# ORD_CH341A.net
KiCad netlist of a schematic drawn in Altium Designer
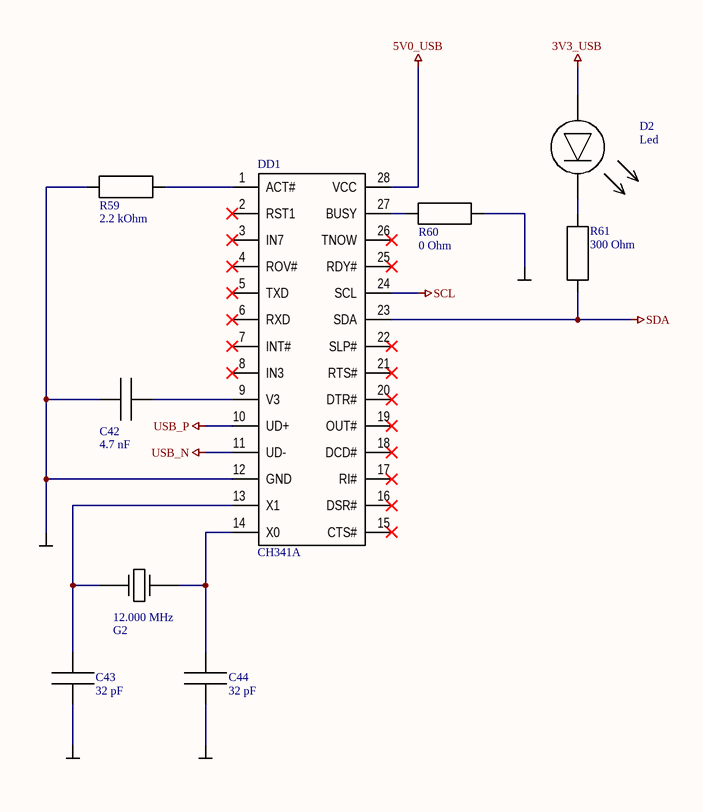
[diagram p0: ORD_CH341A.SchDoc]

(export (version "E")
  (design (tool "Eeschema 10.0.6"))
  (components
    (comp (ref "C42")
      (value "4.7 nF")
      (footprint "C0603[1608]")
      (libsource (lib "Gost_passive_lib") (part "Capacitor"))
    )
    (comp (ref "C43")
      (value "32 pF")
      (footprint "C0603[1608]")
      (libsource (lib "Gost_passive_lib") (part "Capacitor"))
    )
    (comp (ref "C44")
      (value "32 pF")
      (footprint "C0603[1608]")
      (libsource (lib "Gost_passive_lib") (part "Capacitor"))
    )
    (comp (ref "D2") (value "Led") (footprint "LED") (libsource (lib "Gost_passive_lib") (part "Led")))
    (comp (ref "DD1")
      (value "CH341A")
      (footprint "SOIC28")
      (description "USB Bus Convert Chip CH341A")
      (fields (field (name "MANUFACTURER_PART_NUMBER") "FV-1 Reverb IC"))
      (libsource (lib "Gost_active_libs") (part "CH341A"))
    )
    (comp (ref "G2")
      (value "12.000 MHz")
      (footprint "HC-49")
      (libsource (lib "Gost_passive_lib") (part "Crystal_2pin"))
    )
    (comp (ref "R59")
      (value "2.2 kOhm")
      (footprint "R0805[2012]")
      (libsource (lib "Gost_passive_lib") (part "Resistor"))
    )
    (comp (ref "R60")
      (value "0 Ohm")
      (footprint "R0603[1608]")
      (libsource (lib "Gost_passive_lib") (part "Resistor"))
    )
    (comp (ref "R61")
      (value "300 Ohm")
      (footprint "R0603[1608]")
      (libsource (lib "Gost_passive_lib") (part "Resistor"))
    )
  )
  (nets
    (net (code "1") (name "3V3_USB") (class "Default")
      (node (ref "D2") (pin "1") (pinfunction "1_1") (pintype "passive"))
    )
    (net (code "2") (name "5V0_USB") (class "Default")
      (node (ref "DD1") (pin "28") (pinfunction "VCC_28") (pintype "passive"))
    )
    (net (code "3") (name "GND") (class "Default")
      (node (ref "C42") (pin "1") (pinfunction "1_1") (pintype "passive"))
      (node (ref "C43") (pin "1") (pinfunction "1_1") (pintype "passive"))
      (node (ref "C44") (pin "1") (pinfunction "1_1") (pintype "passive"))
      (node (ref "DD1") (pin "12") (pinfunction "GND_12") (pintype "passive"))
      (node (ref "R59") (pin "1") (pinfunction "1_1") (pintype "passive"))
      (node (ref "R60") (pin "2") (pinfunction "2_2") (pintype "passive"))
    )
    (net (code "4") (name "Net-(D2-Pad2)") (class "Default")
      (node (ref "D2") (pin "2") (pinfunction "2_2") (pintype "passive"))
      (node (ref "R61") (pin "2") (pinfunction "2_2") (pintype "passive"))
    )
    (net (code "5") (name "Net-(DD1-ACT#)") (class "Default")
      (node (ref "DD1") (pin "1") (pinfunction "ACT#_1") (pintype "passive"))
      (node (ref "R59") (pin "2") (pinfunction "2_2") (pintype "passive"))
    )
    (net (code "6") (name "Net-(DD1-BUSY)") (class "Default")
      (node (ref "DD1") (pin "27") (pinfunction "BUSY_27") (pintype "passive"))
      (node (ref "R60") (pin "1") (pinfunction "1_1") (pintype "passive"))
    )
    (net (code "7") (name "Net-(DD1-V3)") (class "Default")
      (node (ref "C42") (pin "2") (pinfunction "2_2") (pintype "passive"))
      (node (ref "DD1") (pin "9") (pinfunction "V3_9") (pintype "passive"))
    )
    (net (code "8") (name "Net-(DD1-X0)") (class "Default")
      (node (ref "C44") (pin "2") (pinfunction "2_2") (pintype "passive"))
      (node (ref "DD1") (pin "14") (pinfunction "X0_14") (pintype "passive"))
      (node (ref "G2") (pin "2") (pinfunction "2_2") (pintype "passive"))
    )
    (net (code "9") (name "Net-(DD1-X1)") (class "Default")
      (node (ref "C43") (pin "2") (pinfunction "2_2") (pintype "passive"))
      (node (ref "DD1") (pin "13") (pinfunction "X1_13") (pintype "passive"))
      (node (ref "G2") (pin "1") (pinfunction "1_1") (pintype "passive"))
    )
    (net (code "10") (name "SCL") (class "Default")
      (node (ref "DD1") (pin "24") (pinfunction "SCL_24") (pintype "passive"))
    )
    (net (code "11") (name "SDA") (class "Default")
      (node (ref "DD1") (pin "23") (pinfunction "SDA_23") (pintype "passive"))
      (node (ref "R61") (pin "1") (pinfunction "1_1") (pintype "passive"))
    )
    (net (code "12") (name "USB_N") (class "Default")
      (node (ref "DD1") (pin "11") (pinfunction "UD-_11") (pintype "passive"))
    )
    (net (code "13") (name "USB_P") (class "Default")
      (node (ref "DD1") (pin "10") (pinfunction "UD+_10") (pintype "passive"))
    )
    (net (code "14") (name "unconnected-(DD1-CTS#-Pad15)") (class "Default")
      (node (ref "DD1") (pin "15") (pinfunction "CTS#_15") (pintype "passive+no_connect"))
    )
    (net (code "15") (name "unconnected-(DD1-DCD#-Pad18)") (class "Default")
      (node (ref "DD1") (pin "18") (pinfunction "DCD#_18") (pintype "passive+no_connect"))
    )
    (net (code "16") (name "unconnected-(DD1-DSR#-Pad16)") (class "Default")
      (node (ref "DD1") (pin "16") (pinfunction "DSR#_16") (pintype "passive+no_connect"))
    )
    (net (code "17") (name "unconnected-(DD1-DTR#-Pad20)") (class "Default")
      (node (ref "DD1") (pin "20") (pinfunction "DTR#_20") (pintype "passive+no_connect"))
    )
    (net (code "18") (name "unconnected-(DD1-IN3-Pad8)") (class "Default")
      (node (ref "DD1") (pin "8") (pinfunction "IN3_8") (pintype "passive+no_connect"))
    )
    (net (code "19") (name "unconnected-(DD1-IN7-Pad3)") (class "Default")
      (node (ref "DD1") (pin "3") (pinfunction "IN7_3") (pintype "passive+no_connect"))
    )
    (net (code "20") (name "unconnected-(DD1-INT#-Pad7)") (class "Default")
      (node (ref "DD1") (pin "7") (pinfunction "INT#_7") (pintype "passive+no_connect"))
    )
    (net (code "21") (name "unconnected-(DD1-OUT#-Pad19)") (class "Default")
      (node (ref "DD1") (pin "19") (pinfunction "OUT#_19") (pintype "passive+no_connect"))
    )
    (net (code "22") (name "unconnected-(DD1-RDY#-Pad25)") (class "Default")
      (node (ref "DD1") (pin "25") (pinfunction "RDY#_25") (pintype "passive+no_connect"))
    )
    (net (code "23") (name "unconnected-(DD1-RI#-Pad17)") (class "Default")
      (node (ref "DD1") (pin "17") (pinfunction "RI#_17") (pintype "passive+no_connect"))
    )
    (net (code "24") (name "unconnected-(DD1-ROV#-Pad4)") (class "Default")
      (node (ref "DD1") (pin "4") (pinfunction "ROV#_4") (pintype "passive+no_connect"))
    )
    (net (code "25") (name "unconnected-(DD1-RST1-Pad2)") (class "Default")
      (node (ref "DD1") (pin "2") (pinfunction "RST1_2") (pintype "passive+no_connect"))
    )
    (net (code "26") (name "unconnected-(DD1-RTS#-Pad21)") (class "Default")
      (node (ref "DD1") (pin "21") (pinfunction "RTS#_21") (pintype "passive+no_connect"))
    )
    (net (code "27") (name "unconnected-(DD1-RXD-Pad6)") (class "Default")
      (node (ref "DD1") (pin "6") (pinfunction "RXD_6") (pintype "passive+no_connect"))
    )
    (net (code "28") (name "unconnected-(DD1-SLP#-Pad22)") (class "Default")
      (node (ref "DD1") (pin "22") (pinfunction "SLP#_22") (pintype "passive+no_connect"))
    )
    (net (code "29") (name "unconnected-(DD1-TNOW-Pad26)") (class "Default")
      (node (ref "DD1") (pin "26") (pinfunction "TNOW_26") (pintype "passive+no_connect"))
    )
    (net (code "30") (name "unconnected-(DD1-TXD-Pad5)") (class "Default")
      (node (ref "DD1") (pin "5") (pinfunction "TXD_5") (pintype "passive+no_connect"))
    )
  )
)
